# ME_433.net
KiCad netlist of a schematic drawn in EAGLE
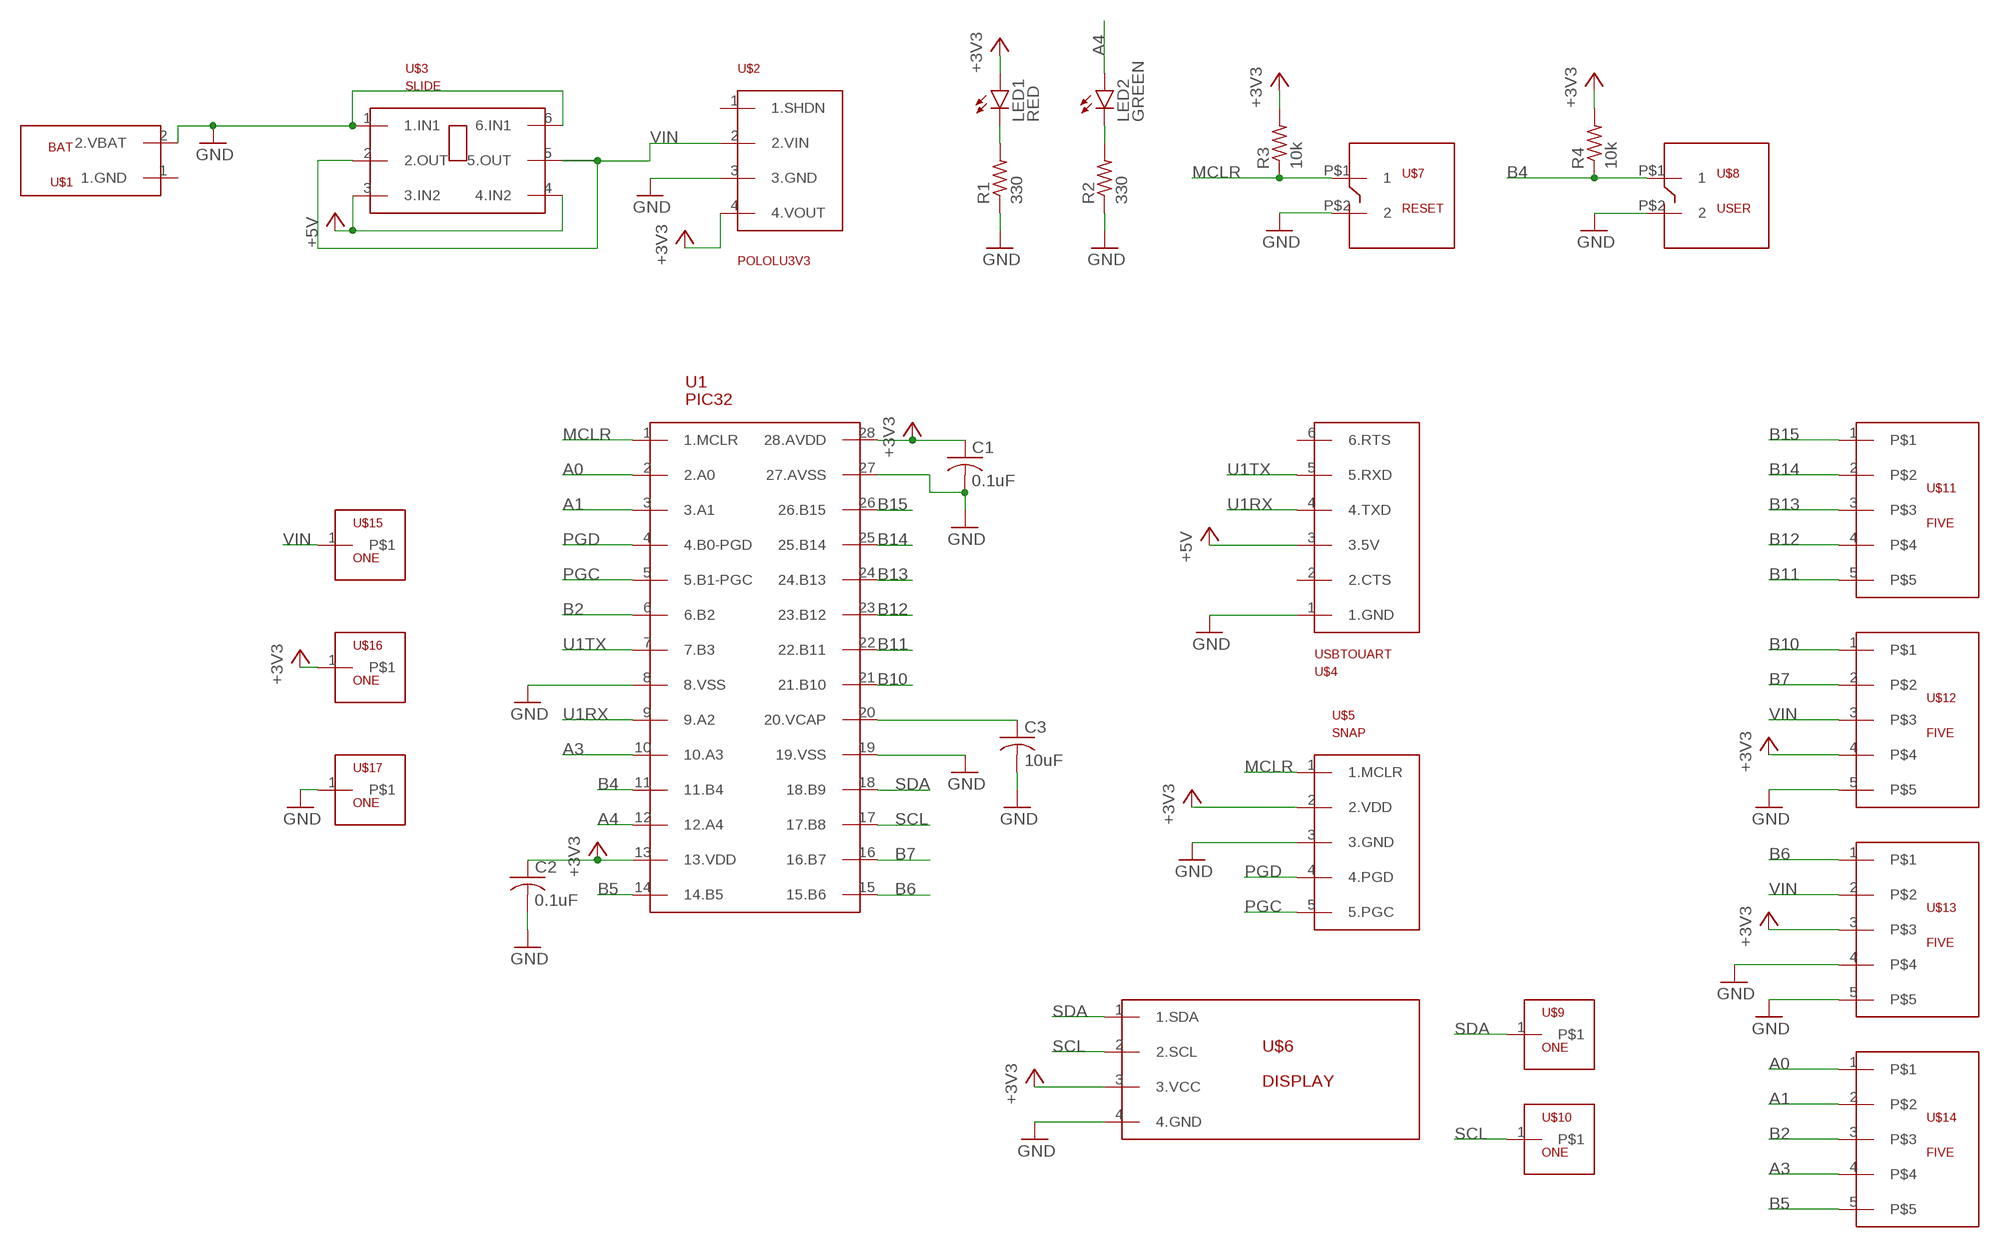
[diagram p0: schematic, sheet 1]

(export (version "E")
  (design (tool "Eeschema 10.0.6"))
  (components
    (comp (ref "C1")
      (value "0.1uF")
      (footprint "eagle-import:C025-024X044")
      (libsource (lib "eagle-import") (part "C-US025-024X044"))
    )
    (comp (ref "C2")
      (value "0.1uF")
      (footprint "eagle-import:C025-024X044")
      (libsource (lib "eagle-import") (part "C-US025-024X044"))
    )
    (comp (ref "C3")
      (value "10uF")
      (footprint "eagle-import:C025-024X044")
      (libsource (lib "eagle-import") (part "C-US025-024X044"))
    )
    (comp (ref "LED1")
      (value "RED")
      (footprint "eagle-import:LED3MM")
      (libsource (lib "eagle-import") (part "LED3MM"))
    )
    (comp (ref "LED2")
      (value "GREEN")
      (footprint "eagle-import:LED3MM")
      (libsource (lib "eagle-import") (part "LED3MM"))
    )
    (comp (ref "R1")
      (value "330")
      (footprint "eagle-import:0207_7")
      (libsource (lib "eagle-import") (part "R-US_0207/7"))
    )
    (comp (ref "R2")
      (value "330")
      (footprint "eagle-import:0207_7")
      (libsource (lib "eagle-import") (part "R-US_0207/7"))
    )
    (comp (ref "R3")
      (value "10k")
      (footprint "eagle-import:0207_7")
      (libsource (lib "eagle-import") (part "R-US_0207/7"))
    )
    (comp (ref "R4")
      (value "10k")
      (footprint "eagle-import:0207_7")
      (libsource (lib "eagle-import") (part "R-US_0207/7"))
    )
    (comp (ref "U$1")
      (value "BAT")
      (footprint "eagle-import:BAT")
      (libsource (lib "eagle-import") (part "BAT"))
    )
    (comp (ref "U$2")
      (value "POLOLU3V3")
      (footprint "eagle-import:POLOLU3V3")
      (libsource (lib "eagle-import") (part "POLOLU3V3"))
    )
    (comp (ref "U$3")
      (value "SLIDE")
      (footprint "eagle-import:SLIDE")
      (libsource (lib "eagle-import") (part "SLIDE"))
    )
    (comp (ref "U$4")
      (value "USBTOUART")
      (footprint "eagle-import:USBTOUART")
      (libsource (lib "eagle-import") (part "USBTOUART"))
    )
    (comp (ref "U$5")
      (value "SNAP")
      (footprint "eagle-import:SNAP")
      (libsource (lib "eagle-import") (part "SNAP"))
    )
    (comp (ref "U$6")
      (value "DISPLAY")
      (footprint "eagle-import:DISPLAY")
      (libsource (lib "eagle-import") (part "DISPLAY"))
    )
    (comp (ref "U$7")
      (value "RESET")
      (footprint "eagle-import:PUSH")
      (libsource (lib "eagle-import") (part "PUSH"))
    )
    (comp (ref "U$8")
      (value "USER")
      (footprint "eagle-import:PUSH")
      (libsource (lib "eagle-import") (part "PUSH"))
    )
    (comp (ref "U$9")
      (value "ONE")
      (footprint "eagle-import:ONE")
      (libsource (lib "eagle-import") (part "ONE"))
    )
    (comp (ref "U$10")
      (value "ONE")
      (footprint "eagle-import:ONE")
      (libsource (lib "eagle-import") (part "ONE"))
    )
    (comp (ref "U$11")
      (value "FIVE")
      (footprint "eagle-import:FIVE")
      (libsource (lib "eagle-import") (part "FIVE"))
    )
    (comp (ref "U$12")
      (value "FIVE")
      (footprint "eagle-import:FIVE")
      (libsource (lib "eagle-import") (part "FIVE"))
    )
    (comp (ref "U$13")
      (value "FIVE")
      (footprint "eagle-import:FIVE")
      (libsource (lib "eagle-import") (part "FIVE"))
    )
    (comp (ref "U$14")
      (value "FIVE")
      (footprint "eagle-import:FIVE")
      (libsource (lib "eagle-import") (part "FIVE"))
    )
    (comp (ref "U$15")
      (value "ONE")
      (footprint "eagle-import:ONE")
      (libsource (lib "eagle-import") (part "ONE"))
    )
    (comp (ref "U$16")
      (value "ONE")
      (footprint "eagle-import:ONE")
      (libsource (lib "eagle-import") (part "ONE"))
    )
    (comp (ref "U$17")
      (value "ONE")
      (footprint "eagle-import:ONE")
      (libsource (lib "eagle-import") (part "ONE"))
    )
    (comp (ref "U1")
      (value "PIC32")
      (footprint "eagle-import:DIL28-3")
      (libsource (lib "eagle-import") (part "PIC32MX170F256B"))
    )
  )
  (nets
    (net (code "1") (name "+3V3") (class "Default")
      (node (ref "C1") (pin "1") (pinfunction "1_1") (pintype "passive"))
      (node (ref "C2") (pin "1") (pinfunction "1_1") (pintype "passive"))
      (node (ref "LED1") (pin "A") (pinfunction "A_A") (pintype "passive"))
      (node (ref "R3") (pin "2") (pinfunction "2_2") (pintype "passive"))
      (node (ref "R4") (pin "2") (pinfunction "2_2") (pintype "passive"))
      (node (ref "U$12") (pin "4") (pinfunction "P$4_4") (pintype "bidirectional"))
      (node (ref "U$13") (pin "3") (pinfunction "P$3_3") (pintype "bidirectional"))
      (node (ref "U$16") (pin "1") (pinfunction "P$1_1") (pintype "bidirectional"))
      (node (ref "U$2") (pin "4") (pinfunction "4.VOUT_4") (pintype "bidirectional"))
      (node (ref "U$5") (pin "2") (pinfunction "2.VDD_2") (pintype "bidirectional"))
      (node (ref "U$6") (pin "3") (pinfunction "3.VCC_3") (pintype "bidirectional"))
      (node (ref "U1") (pin "13") (pinfunction "13.VDD_13") (pintype "bidirectional"))
      (node (ref "U1") (pin "28") (pinfunction "28.AVDD_28") (pintype "bidirectional"))
    )
    (net (code "2") (name "+5V") (class "Default")
      (node (ref "U$3") (pin "3") (pinfunction "3.IN2_3") (pintype "bidirectional"))
      (node (ref "U$3") (pin "4") (pinfunction "4.IN2_4") (pintype "bidirectional"))
      (node (ref "U$4") (pin "3") (pinfunction "3.5V_3") (pintype "bidirectional"))
    )
    (net (code "3") (name "/A0") (class "Default")
      (node (ref "U$14") (pin "1") (pinfunction "P$1_1") (pintype "bidirectional"))
      (node (ref "U1") (pin "2") (pinfunction "2.A0_2") (pintype "bidirectional"))
    )
    (net (code "4") (name "/A1") (class "Default")
      (node (ref "U$14") (pin "2") (pinfunction "P$2_2") (pintype "bidirectional"))
      (node (ref "U1") (pin "3") (pinfunction "3.A1_3") (pintype "bidirectional"))
    )
    (net (code "5") (name "/A3") (class "Default")
      (node (ref "U$14") (pin "4") (pinfunction "P$4_4") (pintype "bidirectional"))
      (node (ref "U1") (pin "10") (pinfunction "10.A3_10") (pintype "bidirectional"))
    )
    (net (code "6") (name "/A4") (class "Default")
      (node (ref "LED2") (pin "A") (pinfunction "A_A") (pintype "passive"))
      (node (ref "U1") (pin "12") (pinfunction "12.A4_12") (pintype "bidirectional"))
    )
    (net (code "7") (name "/B2") (class "Default")
      (node (ref "U$14") (pin "3") (pinfunction "P$3_3") (pintype "bidirectional"))
      (node (ref "U1") (pin "6") (pinfunction "6.B2_6") (pintype "bidirectional"))
    )
    (net (code "8") (name "/B4") (class "Default")
      (node (ref "R4") (pin "1") (pinfunction "1_1") (pintype "passive"))
      (node (ref "U$8") (pin "P$1") (pinfunction "1_P$1") (pintype "bidirectional"))
      (node (ref "U1") (pin "11") (pinfunction "11.B4_11") (pintype "bidirectional"))
    )
    (net (code "9") (name "/B5") (class "Default")
      (node (ref "U$14") (pin "5") (pinfunction "P$5_5") (pintype "bidirectional"))
      (node (ref "U1") (pin "14") (pinfunction "14.B5_14") (pintype "bidirectional"))
    )
    (net (code "10") (name "/B6") (class "Default")
      (node (ref "U$13") (pin "1") (pinfunction "P$1_1") (pintype "bidirectional"))
      (node (ref "U1") (pin "15") (pinfunction "15.B6_15") (pintype "bidirectional"))
    )
    (net (code "11") (name "/B7") (class "Default")
      (node (ref "U$12") (pin "2") (pinfunction "P$2_2") (pintype "bidirectional"))
      (node (ref "U1") (pin "16") (pinfunction "16.B7_16") (pintype "bidirectional"))
    )
    (net (code "12") (name "/B10") (class "Default")
      (node (ref "U$12") (pin "1") (pinfunction "P$1_1") (pintype "bidirectional"))
      (node (ref "U1") (pin "21") (pinfunction "21.B10_21") (pintype "bidirectional"))
    )
    (net (code "13") (name "/B11") (class "Default")
      (node (ref "U$11") (pin "5") (pinfunction "P$5_5") (pintype "bidirectional"))
      (node (ref "U1") (pin "22") (pinfunction "22.B11_22") (pintype "bidirectional"))
    )
    (net (code "14") (name "/B12") (class "Default")
      (node (ref "U$11") (pin "4") (pinfunction "P$4_4") (pintype "bidirectional"))
      (node (ref "U1") (pin "23") (pinfunction "23.B12_23") (pintype "bidirectional"))
    )
    (net (code "15") (name "/B13") (class "Default")
      (node (ref "U$11") (pin "3") (pinfunction "P$3_3") (pintype "bidirectional"))
      (node (ref "U1") (pin "24") (pinfunction "24.B13_24") (pintype "bidirectional"))
    )
    (net (code "16") (name "/B14") (class "Default")
      (node (ref "U$11") (pin "2") (pinfunction "P$2_2") (pintype "bidirectional"))
      (node (ref "U1") (pin "25") (pinfunction "25.B14_25") (pintype "bidirectional"))
    )
    (net (code "17") (name "/B15") (class "Default")
      (node (ref "U$11") (pin "1") (pinfunction "P$1_1") (pintype "bidirectional"))
      (node (ref "U1") (pin "26") (pinfunction "26.B15_26") (pintype "bidirectional"))
    )
    (net (code "18") (name "/MCLR") (class "Default")
      (node (ref "R3") (pin "1") (pinfunction "1_1") (pintype "passive"))
      (node (ref "U$5") (pin "1") (pinfunction "1.MCLR_1") (pintype "bidirectional"))
      (node (ref "U$7") (pin "P$1") (pinfunction "1_P$1") (pintype "bidirectional"))
      (node (ref "U1") (pin "1") (pinfunction "1.MCLR_1") (pintype "bidirectional"))
    )
    (net (code "19") (name "/PGC") (class "Default")
      (node (ref "U$5") (pin "5") (pinfunction "5.PGC_5") (pintype "bidirectional"))
      (node (ref "U1") (pin "5") (pinfunction "5.B1-PGC_5") (pintype "bidirectional"))
    )
    (net (code "20") (name "/PGD") (class "Default")
      (node (ref "U$5") (pin "4") (pinfunction "4.PGD_4") (pintype "bidirectional"))
      (node (ref "U1") (pin "4") (pinfunction "4.B0-PGD_4") (pintype "bidirectional"))
    )
    (net (code "21") (name "/SCL") (class "Default")
      (node (ref "U$10") (pin "1") (pinfunction "P$1_1") (pintype "bidirectional"))
      (node (ref "U$6") (pin "2") (pinfunction "2.SCL_2") (pintype "bidirectional"))
      (node (ref "U1") (pin "17") (pinfunction "17.B8_17") (pintype "bidirectional"))
    )
    (net (code "22") (name "/SDA") (class "Default")
      (node (ref "U$6") (pin "1") (pinfunction "1.SDA_1") (pintype "bidirectional"))
      (node (ref "U$9") (pin "1") (pinfunction "P$1_1") (pintype "bidirectional"))
      (node (ref "U1") (pin "18") (pinfunction "18.B9_18") (pintype "bidirectional"))
    )
    (net (code "23") (name "/U1RX") (class "Default")
      (node (ref "U$4") (pin "4") (pinfunction "4.TXD_4") (pintype "bidirectional"))
      (node (ref "U1") (pin "9") (pinfunction "9.A2_9") (pintype "bidirectional"))
    )
    (net (code "24") (name "/U1TX") (class "Default")
      (node (ref "U$4") (pin "5") (pinfunction "5.RXD_5") (pintype "bidirectional"))
      (node (ref "U1") (pin "7") (pinfunction "7.B3_7") (pintype "bidirectional"))
    )
    (net (code "25") (name "/VIN") (class "Default")
      (node (ref "U$12") (pin "3") (pinfunction "P$3_3") (pintype "bidirectional"))
      (node (ref "U$13") (pin "2") (pinfunction "P$2_2") (pintype "bidirectional"))
      (node (ref "U$15") (pin "1") (pinfunction "P$1_1") (pintype "bidirectional"))
      (node (ref "U$2") (pin "2") (pinfunction "2.VIN_2") (pintype "bidirectional"))
      (node (ref "U$3") (pin "2") (pinfunction "2.OUT_2") (pintype "bidirectional"))
      (node (ref "U$3") (pin "5") (pinfunction "5.OUT_5") (pintype "bidirectional"))
    )
    (net (code "26") (name "GND") (class "Default")
      (node (ref "C1") (pin "2") (pinfunction "2_2") (pintype "passive"))
      (node (ref "C2") (pin "2") (pinfunction "2_2") (pintype "passive"))
      (node (ref "C3") (pin "2") (pinfunction "2_2") (pintype "passive"))
      (node (ref "R1") (pin "1") (pinfunction "1_1") (pintype "passive"))
      (node (ref "R2") (pin "1") (pinfunction "1_1") (pintype "passive"))
      (node (ref "U$1") (pin "2") (pinfunction "2.VBAT_2") (pintype "bidirectional"))
      (node (ref "U$12") (pin "5") (pinfunction "P$5_5") (pintype "bidirectional"))
      (node (ref "U$13") (pin "4") (pinfunction "P$4_4") (pintype "bidirectional"))
      (node (ref "U$13") (pin "5") (pinfunction "P$5_5") (pintype "bidirectional"))
      (node (ref "U$17") (pin "1") (pinfunction "P$1_1") (pintype "bidirectional"))
      (node (ref "U$2") (pin "3") (pinfunction "3.GND_3") (pintype "bidirectional"))
      (node (ref "U$3") (pin "1") (pinfunction "1.IN1_1") (pintype "bidirectional"))
      (node (ref "U$3") (pin "6") (pinfunction "6.IN1_6") (pintype "bidirectional"))
      (node (ref "U$4") (pin "1") (pinfunction "1.GND_1") (pintype "bidirectional"))
      (node (ref "U$5") (pin "3") (pinfunction "3.GND_3") (pintype "bidirectional"))
      (node (ref "U$6") (pin "4") (pinfunction "4.GND_4") (pintype "bidirectional"))
      (node (ref "U$7") (pin "P$2") (pinfunction "2_P$2") (pintype "bidirectional"))
      (node (ref "U$8") (pin "P$2") (pinfunction "2_P$2") (pintype "bidirectional"))
      (node (ref "U1") (pin "19") (pinfunction "19.VSS_19") (pintype "bidirectional"))
      (node (ref "U1") (pin "27") (pinfunction "27.AVSS_27") (pintype "bidirectional"))
      (node (ref "U1") (pin "8") (pinfunction "8.VSS_8") (pintype "bidirectional"))
    )
    (net (code "27") (name "Net-(LED1-C)") (class "Default")
      (node (ref "LED1") (pin "K") (pinfunction "C_K") (pintype "passive"))
      (node (ref "R1") (pin "2") (pinfunction "2_2") (pintype "passive"))
    )
    (net (code "28") (name "Net-(LED2-C)") (class "Default")
      (node (ref "LED2") (pin "K") (pinfunction "C_K") (pintype "passive"))
      (node (ref "R2") (pin "2") (pinfunction "2_2") (pintype "passive"))
    )
    (net (code "29") (name "Net-(U1-20.VCAP)") (class "Default")
      (node (ref "C3") (pin "1") (pinfunction "1_1") (pintype "passive"))
      (node (ref "U1") (pin "20") (pinfunction "20.VCAP_20") (pintype "bidirectional"))
    )
    (net (code "30") (name "unconnected-(U$1-1.GND-Pad1)") (class "Default")
      (node (ref "U$1") (pin "1") (pinfunction "1.GND_1") (pintype "bidirectional"))
    )
    (net (code "31") (name "unconnected-(U$2-1.SHDN-Pad1)") (class "Default")
      (node (ref "U$2") (pin "1") (pinfunction "1.SHDN_1") (pintype "bidirectional"))
    )
    (net (code "32") (name "unconnected-(U$4-2.CTS-Pad2)") (class "Default")
      (node (ref "U$4") (pin "2") (pinfunction "2.CTS_2") (pintype "bidirectional"))
    )
    (net (code "33") (name "unconnected-(U$4-6.RTS-Pad6)") (class "Default")
      (node (ref "U$4") (pin "6") (pinfunction "6.RTS_6") (pintype "bidirectional"))
    )
  )
)
